# 5V_Buck.net
KiCad netlist of a schematic drawn in Altium Designer
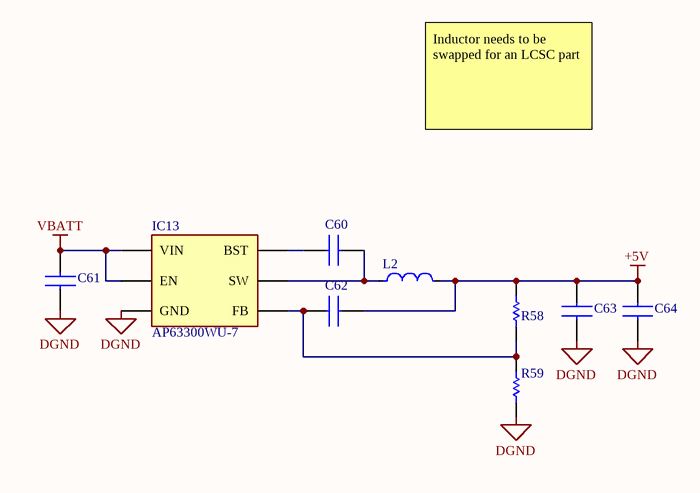
[diagram p0: +5V Buck.SchDoc]

(export (version "E")
  (design (tool "Eeschema 10.0.6"))
  (components
    (comp (ref "C60")
      (value "0603,X7R,100nF,50V,10%")
      (footprint "CAPC1608X90N")
      (description "50V 100nF X7R ±10% 0603 Multilayer Ceramic Capacitors MLCC - SMD/SMT ROHS")
      (fields (field (name "LCSC PART #") "C14663") (field (name "MANU PART #") "CC0603KRX7R9BB104"))
      (libsource (lib "flight-controller") (part "CC0603KRX7R9BB104"))
    )
    (comp (ref "C61")
      (value "0805,X7R,10uF,25V,10%")
      (footprint "CAPC2012X145N")
      (description "10uF ±10% 25V Ceramic Capacitor X7R 0805")
      (fields (field (name "LCSC PART #") "C3039694") (field (name "MANU PART #") "CL21B106KAYQNNE"))
      (libsource (lib "flight-controller") (part "CL21B106KAYQNNE"))
    )
    (comp (ref "C62")
      (value "0603,NP0,47pF,50V,5%")
      (footprint "CAPC1608X90N")
      (description "47 pF ±5% 50V Ceramic Capacitor C0G, NP0 0603 (1608 Metric)")
      (fields (field (name "MANU PART #") "CC0603JRNPO9BN470") (field (name "LCSC PART #") "C105622"))
      (libsource (lib "flight-controller") (part "CC0603JRNPO9BN470"))
    )
    (comp (ref "C63")
      (value "0805,X5R,22uF,25V,20%")
      (footprint "CAPC2012X145N")
      (description "22uF ±20% 25V Ceramic Capacitor X5R 0805")
      (fields (field (name "LCSC PART #") "C602037") (field (name "MANU PART #") "CL21A226MAYNNNE"))
      (libsource (lib "flight-controller") (part "CL21A226MAYNNNE"))
    )
    (comp (ref "C64")
      (value "0805,X5R,22uF,25V,20%")
      (footprint "CAPC2012X145N")
      (description "22uF ±20% 25V Ceramic Capacitor X5R 0805")
      (fields (field (name "LCSC PART #") "C602037") (field (name "MANU PART #") "CL21A226MAYNNNE"))
      (libsource (lib "flight-controller") (part "CL21A226MAYNNNE"))
    )
    (comp (ref "IC13")
      (value "AP63300WU-7")
      (footprint "SOT95P280X90-6N")
      (description "DCDC CONV HV BUCK TSOT26")
      (fields (field (name "MOUSER PART NUMBER") "621-AP63300WU-7"))
      (libsource (lib "flight-controller") (part "AP63300WU-7"))
    )
    (comp (ref "L2")
      (value "FXL0630-6R8-M")
      (footprint "FXL0630-6R8-M")
      (description "48mΩ 5A 6.8uH 6A Molded Inductor ±20% SMD,7x6.6mm Power Inductors ROHS")
      (fields (field (name "MANUFACTURER") "cjiang (Changjiang Microelectronics Tech)"))
      (libsource (lib "flight-controller") (part "FXL0630-6R8-M"))
    )
    (comp (ref "R58")
      (value "FRC0603F1583TS")
      (footprint "FRC0603F1583TS")
      (fields (field (name "MANUFACTURER") "FOJAN"))
      (libsource (lib "flight-controller") (part "FRC0603F1583TS"))
    )
    (comp (ref "R59")
      (value "RC0603FR-0730K1L")
      (footprint "RC0603FR-0730K1L")
      (fields (field (name "MANUFACTURER") "YAGEO"))
      (libsource (lib "flight-controller") (part "RC0603FR-0730K1L"))
    )
  )
  (nets
    (net (code "1") (name "+5V") (class "Default")
      (node (ref "C62") (pin "1") (pinfunction "1_1") (pintype "passive"))
      (node (ref "C63") (pin "2") (pinfunction "2_2") (pintype "passive"))
      (node (ref "C64") (pin "2") (pinfunction "2_2") (pintype "passive"))
      (node (ref "L2") (pin "2") (pinfunction "2_2") (pintype "passive"))
      (node (ref "R58") (pin "2") (pinfunction "2_2") (pintype "passive"))
    )
    (net (code "2") (name "DGND") (class "Default")
      (node (ref "C61") (pin "2") (pinfunction "2_2") (pintype "passive"))
      (node (ref "C63") (pin "1") (pinfunction "1_1") (pintype "passive"))
      (node (ref "C64") (pin "1") (pinfunction "1_1") (pintype "passive"))
      (node (ref "IC13") (pin "4") (pinfunction "GND_4") (pintype "passive"))
      (node (ref "R59") (pin "1") (pinfunction "1_1") (pintype "passive"))
    )
    (net (code "3") (name "Net-(IC13-BST)") (class "Default")
      (node (ref "C60") (pin "1") (pinfunction "1_1") (pintype "passive"))
      (node (ref "IC13") (pin "6") (pinfunction "BST_6") (pintype "passive"))
    )
    (net (code "4") (name "Net-(IC13-FB)") (class "Default")
      (node (ref "C62") (pin "2") (pinfunction "2_2") (pintype "passive"))
      (node (ref "IC13") (pin "1") (pinfunction "FB_1") (pintype "passive"))
      (node (ref "R58") (pin "1") (pinfunction "1_1") (pintype "passive"))
      (node (ref "R59") (pin "2") (pinfunction "2_2") (pintype "passive"))
    )
    (net (code "5") (name "Net-(IC13-SW)") (class "Default")
      (node (ref "C60") (pin "2") (pinfunction "2_2") (pintype "passive"))
      (node (ref "IC13") (pin "5") (pinfunction "SW_5") (pintype "passive"))
      (node (ref "L2") (pin "1") (pinfunction "1_1") (pintype "passive"))
    )
    (net (code "6") (name "VBATT") (class "Default")
      (node (ref "C61") (pin "1") (pinfunction "1_1") (pintype "passive"))
      (node (ref "IC13") (pin "2") (pinfunction "EN_2") (pintype "passive"))
      (node (ref "IC13") (pin "3") (pinfunction "VIN_3") (pintype "passive"))
    )
  )
)
